# iNixie-Kit.net
KiCad netlist of a schematic drawn in Altium Designer
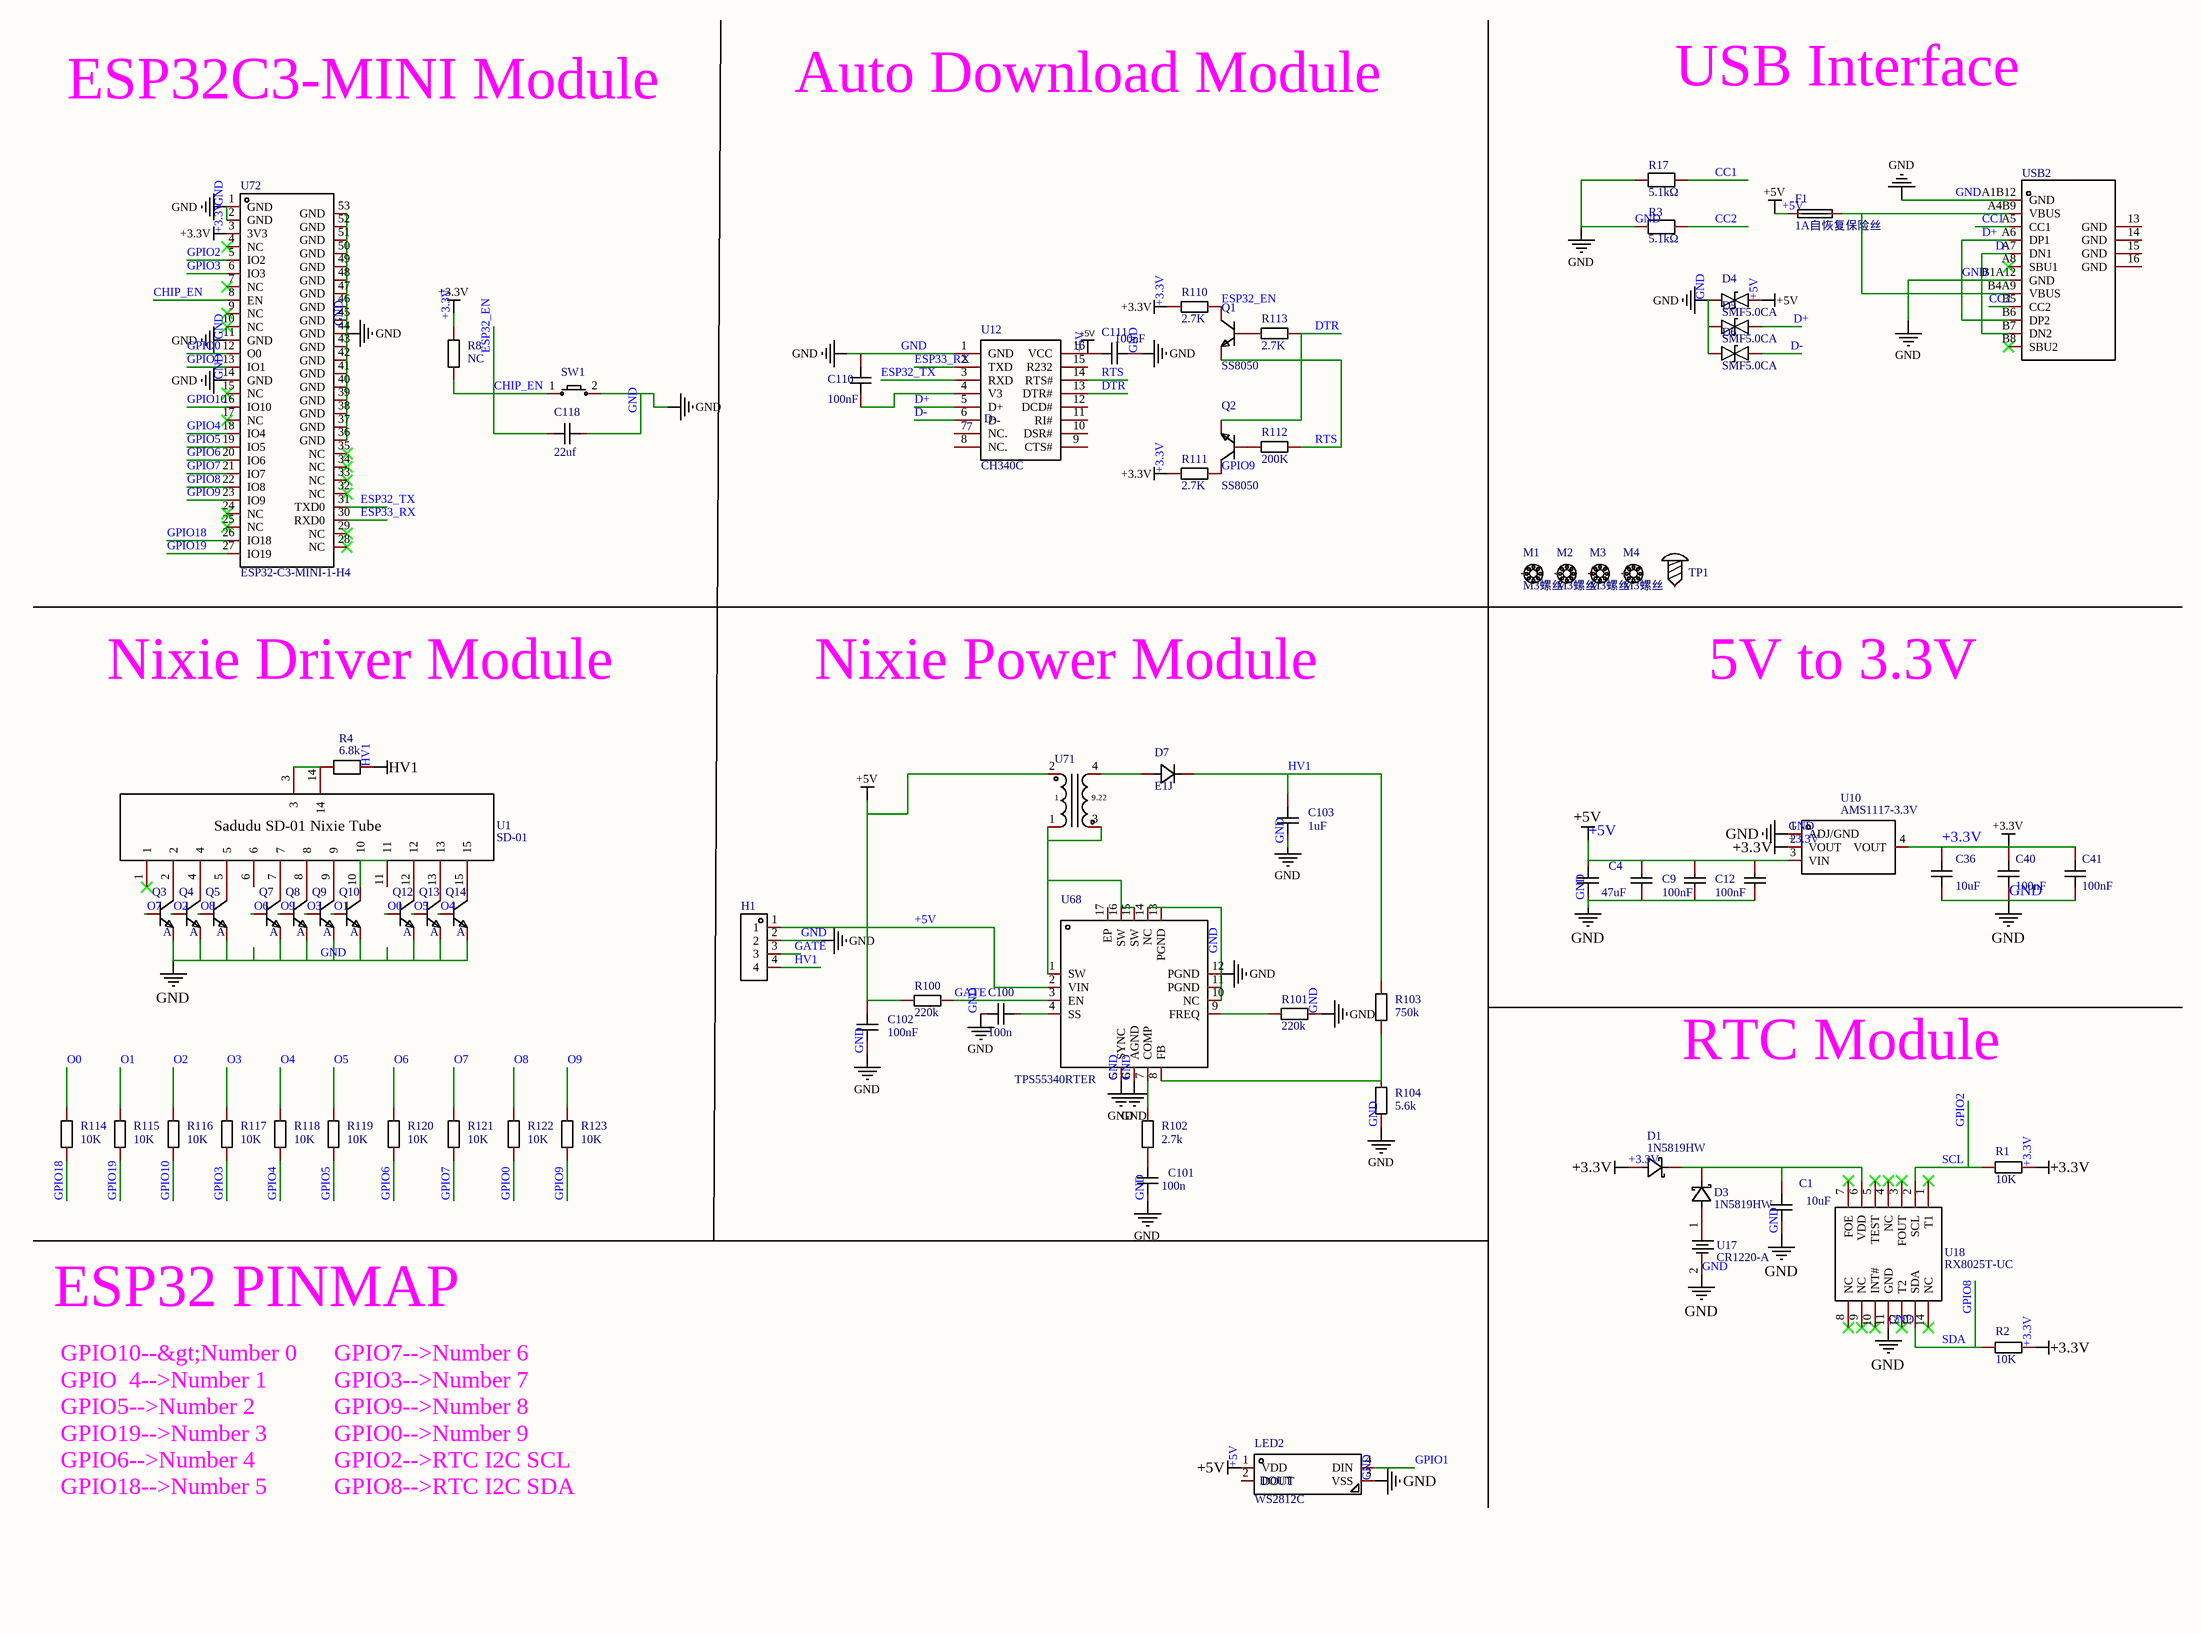
[diagram p0: iNixie-Kit.schdoc]

(export (version "E")
  (design (tool "Eeschema 10.0.6"))
  (components
    (comp (ref "C1")
      (value "10uF")
      (description "容值:10uF;精度:±20%;额定电压:10V;温度系数:X5R;")
      (fields
        (field (name "MANUFACTURER") "SAMSUNG(三星)")
        (field (name "MANUFACTURER PART") "CL10A106MP8NNNC")
      )
      (libsource (lib "altium-import") (part "root_1_CL10A106MP8NNNC_"))
    )
    (comp (ref "C4")
      (value "47uF")
      (description "容值:100nF;精度:±10%;额定电压:50V;温度系数:X7R;")
      (fields (field (name "NAME") "47uF"))
      (libsource (lib "altium-import") (part "root_1_CAP_1206_"))
    )
    (comp (ref "C9")
      (value "100nF")
      (description "容值:100nF;精度:±10%;额定电压:50V;温度系数:X7R;")
      (fields (field (name "MANUFACTURER") "FH(风华)") (field (name "MANUFACTURER PART") "0603B104K500NT"))
      (libsource (lib "altium-import") (part "root_3_0603B104K500NT_"))
    )
    (comp (ref "C12")
      (value "100nF")
      (description "容值:100nF;精度:±10%;额定电压:50V;温度系数:X7R;")
      (fields (field (name "MANUFACTURER") "FH(风华)") (field (name "MANUFACTURER PART") "0603B104K500NT"))
      (libsource (lib "altium-import") (part "root_3_0603B104K500NT_"))
    )
    (comp (ref "C13")
      (value "0603B104K500NT")
      (description "容值:100nF;精度:±10%;额定电压:50V;温度系数:X7R;")
      (fields (field (name "MANUFACTURER") "FH(风华)") (field (name "TOLERANCE") "±10%"))
      (libsource (lib "altium-import") (part "root_3_0603B104K500NT_"))
    )
    (comp (ref "C36")
      (value "10uF")
      (description "容值:10uF;精度:±20%;额定电压:10V;温度系数:X5R;")
      (fields
        (field (name "MANUFACTURER") "SAMSUNG(三星)")
        (field (name "MANUFACTURER PART") "CL10A106MP8NNNC")
      )
      (libsource (lib "altium-import") (part "root_1_CL10A106MP8NNNC_"))
    )
    (comp (ref "C40")
      (value "100nF")
      (description "容值:100nF;精度:±10%;额定电压:16V;温度系数:X7R;")
      (fields (field (name "NAME") "100nF"))
      (libsource (lib "altium-import") (part "root_1_CAP_0402_"))
    )
    (comp (ref "C41")
      (value "100nF")
      (description "容值:100nF;精度:±10%;额定电压:16V;温度系数:X7R;")
      (fields (field (name "NAME") "100nF"))
      (libsource (lib "altium-import") (part "root_1_CAP_0402_"))
    )
    (comp (ref "C100")
      (value "100n")
      (fields (field (name "NAME") "100n"))
      (libsource (lib "altium-import") (part "root_0_C0402_"))
    )
    (comp (ref "C101")
      (value "100n")
      (fields (field (name "NAME") "100n"))
      (libsource (lib "altium-import") (part "root_1_C0402_"))
    )
    (comp (ref "C102")
      (value "100nF")
      (fields (field (name "NAME") "100nF"))
      (libsource (lib "altium-import") (part "root_1_CAP_0603_"))
    )
    (comp (ref "C103")
      (value "1uF")
      (description "容值:1uF;精度:±10%;额定电压:50V;材质(温度系数):X7R;")
      (fields
        (field (name "NAME") "1uF")
        (field (name "MANUFACTURER") "SAMSUNG(三星)")
        (field (name "MANUFACTURER PART") "CL31B105KBHNNNE")
      )
      (libsource (lib "altium-import") (part "root_1_CL31B105KBHNNNE_"))
    )
    (comp (ref "C110")
      (value "100nF")
      (description "容值:100nF;精度:±10%;额定电压:50V;温度系数:X7R;")
      (fields (field (name "NAME") "100nF"))
      (libsource (lib "altium-import") (part "root_1_CAP_0603_"))
    )
    (comp (ref "C111")
      (value "100nF")
      (description "容值:100nF;精度:±10%;额定电压:50V;温度系数:X7R;")
      (fields (field (name "NAME") "100nF"))
      (libsource (lib "altium-import") (part "root_2_CAP_0603_"))
    )
    (comp (ref "C118")
      (value "22uf")
      (description "容值:100nF;精度:±10%;额定电压:16V;温度系数:X7R;")
      (fields (field (name "NAME") "22uf"))
      (libsource (lib "altium-import") (part "root_2_CAP_0402_"))
    )
    (comp (ref "D1")
      (value "1N5819HW")
      (fields (field (name "NAME") "1N5819HW") (field (name "MANUFACTURER") "TECH PUBLIC(台舟)"))
      (libsource (lib "altium-import") (part "root_2_1N5819HW_"))
    )
    (comp (ref "D3")
      (value "1N5819HW")
      (fields (field (name "NAME") "1N5819HW") (field (name "MANUFACTURER") "TECH PUBLIC(台舟)"))
      (libsource (lib "altium-import") (part "root_3_1N5819HW_"))
    )
    (comp (ref "D4")
      (value "SMF5.0CA")
      (description "极性:双向;反向截止电压(Vrwm):5V;击穿电压:6.4V;反向漏电流(Ir):800uA;峰值脉冲电流(Ipp)@10/1000s:21.7A;最大钳位电压:9.2V;")
      (fields (field (name "NAME") "SMF5.0CA") (field (name "MANUFACTURER") "FUXINSEMI(富芯森美)"))
      (libsource (lib "altium-import") (part "root_0_mirrored_SMF5.0CA_C908214_"))
    )
    (comp (ref "D5")
      (value "SMF5.0CA")
      (description "极性:双向;反向截止电压(Vrwm):5V;击穿电压:6.4V;反向漏电流(Ir):800uA;峰值脉冲电流(Ipp)@10/1000s:21.7A;最大钳位电压:9.2V;")
      (fields (field (name "NAME") "SMF5.0CA") (field (name "MANUFACTURER") "FUXINSEMI(富芯森美)"))
      (libsource (lib "altium-import") (part "root_0_mirrored_SMF5.0CA_C908214_"))
    )
    (comp (ref "D6")
      (value "SMF5.0CA")
      (description "极性:双向;反向截止电压(Vrwm):5V;击穿电压:6.4V;反向漏电流(Ir):800uA;峰值脉冲电流(Ipp)@10/1000s:21.7A;最大钳位电压:9.2V;")
      (fields (field (name "NAME") "SMF5.0CA") (field (name "MANUFACTURER") "FUXINSEMI(富芯森美)"))
      (libsource (lib "altium-import") (part "root_0_mirrored_SMF5.0CA_C908214_"))
    )
    (comp (ref "D7")
      (value "E1J")
      (description "二极管配置:-;直流反向耐压(Vr):600V;平均整流电流(Io):1A;正向压降(Vf):1.7V@1A;反向恢复时间(trr):35ns;")
      (fields (field (name "NAME") "E1J") (field (name "MANUFACTURER") "LGE(鲁光)"))
      (libsource (lib "altium-import") (part "root_2_E1J_"))
    )
    (comp (ref "F1")
      (value "1A自恢复保险丝")
      (fields (field (name "NAME") "1A自恢复保险丝"))
      (libsource (lib "altium-import") (part "root_0_1A自恢复保险丝_"))
    )
    (comp (ref "H1")
      (value "HDR-M_2.54_1x4P")
      (libsource (lib "altium-import") (part "root_0_mirrored_HDR-M_2.54_1x4P_"))
    )
    (comp (ref "LED2")
      (value "WS2812C")
      (description "发光颜色:RGB三色;")
      (fields
        (field (name "NAME") "WS2812C")
        (field (name "MANUFACTURER") "worldsemi")
        (field (name "NAME_1") "DOUT")
      )
      (libsource (lib "altium-import") (part "root_0_WS2812C_"))
    )
    (comp (ref "M1")
      (value "M3螺丝")
      (fields (field (name "NAME") "M3螺丝"))
      (libsource (lib "altium-import") (part "root_0_M3螺丝_"))
    )
    (comp (ref "M2")
      (value "M3螺丝")
      (fields (field (name "NAME") "M3螺丝"))
      (libsource (lib "altium-import") (part "root_0_M3螺丝_"))
    )
    (comp (ref "M3")
      (value "M3螺丝")
      (fields (field (name "NAME") "M3螺丝"))
      (libsource (lib "altium-import") (part "root_0_M3螺丝_"))
    )
    (comp (ref "M4")
      (value "M3螺丝")
      (fields (field (name "NAME") "M3螺丝"))
      (libsource (lib "altium-import") (part "root_0_M3螺丝_"))
    )
    (comp (ref "Q1")
      (value "SS8050")
      (fields (field (name "NAME") "SS8050") (field (name "MANUFACTURER") "CJ(江苏长电/长晶)"))
      (libsource (lib "altium-import") (part "root_0_mirrored_SS8050_C2150_"))
    )
    (comp (ref "Q2")
      (value "SS8050")
      (fields (field (name "NAME") "SS8050") (field (name "MANUFACTURER") "CJ(江苏长电/长晶)"))
      (libsource (lib "altium-import") (part "root_2_SS8050_C2150_"))
    )
    (comp (ref "Q3")
      (value "A")
      (fields
        (field (name "NAME") "A")
        (field (name "MANUFACTURER") "UTC")
        (field (name "MANUFACTURER PART") "MMBTA42G-AE3-R")
      )
      (libsource (lib "altium-import") (part "root_0_MMBTA42G-AE3-R_"))
    )
    (comp (ref "Q4")
      (value "A")
      (fields
        (field (name "NAME") "A")
        (field (name "MANUFACTURER") "UTC")
        (field (name "MANUFACTURER PART") "MMBTA42G-AE3-R")
      )
      (libsource (lib "altium-import") (part "root_0_MMBTA42G-AE3-R_"))
    )
    (comp (ref "Q5")
      (value "A")
      (fields
        (field (name "NAME") "A")
        (field (name "MANUFACTURER") "UTC")
        (field (name "MANUFACTURER PART") "MMBTA42G-AE3-R")
      )
      (libsource (lib "altium-import") (part "root_0_MMBTA42G-AE3-R_"))
    )
    (comp (ref "Q7")
      (value "A")
      (fields
        (field (name "NAME") "A")
        (field (name "MANUFACTURER") "UTC")
        (field (name "MANUFACTURER PART") "MMBTA42G-AE3-R")
      )
      (libsource (lib "altium-import") (part "root_0_MMBTA42G-AE3-R_"))
    )
    (comp (ref "Q8")
      (value "A")
      (fields
        (field (name "NAME") "A")
        (field (name "MANUFACTURER") "UTC")
        (field (name "MANUFACTURER PART") "MMBTA42G-AE3-R")
      )
      (libsource (lib "altium-import") (part "root_0_MMBTA42G-AE3-R_"))
    )
    (comp (ref "Q9")
      (value "A")
      (fields
        (field (name "NAME") "A")
        (field (name "MANUFACTURER") "UTC")
        (field (name "MANUFACTURER PART") "MMBTA42G-AE3-R")
      )
      (libsource (lib "altium-import") (part "root_0_MMBTA42G-AE3-R_"))
    )
    (comp (ref "Q10")
      (value "A")
      (fields
        (field (name "NAME") "A")
        (field (name "MANUFACTURER") "UTC")
        (field (name "MANUFACTURER PART") "MMBTA42G-AE3-R")
      )
      (libsource (lib "altium-import") (part "root_0_MMBTA42G-AE3-R_"))
    )
    (comp (ref "Q12")
      (value "A")
      (fields
        (field (name "NAME") "A")
        (field (name "MANUFACTURER") "UTC")
        (field (name "MANUFACTURER PART") "MMBTA42G-AE3-R")
      )
      (libsource (lib "altium-import") (part "root_0_MMBTA42G-AE3-R_"))
    )
    (comp (ref "Q13")
      (value "A")
      (fields
        (field (name "NAME") "A")
        (field (name "MANUFACTURER") "UTC")
        (field (name "MANUFACTURER PART") "MMBTA42G-AE3-R")
      )
      (libsource (lib "altium-import") (part "root_0_MMBTA42G-AE3-R_"))
    )
    (comp (ref "Q14")
      (value "A")
      (fields
        (field (name "NAME") "A")
        (field (name "MANUFACTURER") "UTC")
        (field (name "MANUFACTURER PART") "MMBTA42G-AE3-R")
      )
      (libsource (lib "altium-import") (part "root_0_MMBTA42G-AE3-R_"))
    )
    (comp (ref "R1")
      (value "10K")
      (fields (field (name "NAME") "10K"))
      (libsource (lib "altium-import") (part "root_0_Res_0402_"))
    )
    (comp (ref "R2")
      (value "10K")
      (fields (field (name "NAME") "10K"))
      (libsource (lib "altium-import") (part "root_0_Res_0402_"))
    )
    (comp (ref "R3")
      (value "5.1kΩ")
      (description "温度系数:±25ppm/℃;精度:±0.1%;功率:100mW;阻值:5.1kΩ;最大工作电压:50V;工作温度范围:-55℃~+155℃;")
      (fields (field (name "MANUFACTURER") "FH(风华)") (field (name "MANUFACTURER PART") "TD03G5101BT"))
      (libsource (lib "altium-import") (part "root_2_mirrored_td03g5101bt_"))
    )
    (comp (ref "R4")
      (value "6.8k")
      (fields (field (name "NAME") "6.8k"))
      (libsource (lib "altium-import") (part "root_0_5k_"))
    )
    (comp (ref "R8")
      (value "NC")
      (fields (field (name "NAME") "NC"))
      (libsource (lib "altium-import") (part "root_1_Res_0402_"))
    )
    (comp (ref "R17")
      (value "5.1kΩ")
      (description "温度系数:±25ppm/℃;精度:±0.1%;功率:100mW;阻值:5.1kΩ;最大工作电压:50V;工作温度范围:-55℃~+155℃;")
      (fields (field (name "MANUFACTURER") "FH(风华)") (field (name "MANUFACTURER PART") "TD03G5101BT"))
      (libsource (lib "altium-import") (part "root_2_mirrored_td03g5101bt_"))
    )
    (comp (ref "R100")
      (value "220k")
      (fields (field (name "NAME") "220k"))
      (libsource (lib "altium-import") (part "root_0_Res_0402_"))
    )
    (comp (ref "R101")
      (value "220k")
      (fields (field (name "NAME") "220k"))
      (libsource (lib "altium-import") (part "root_0_Res_0402_"))
    )
    (comp (ref "R102")
      (value "2.7k")
      (fields (field (name "NAME") "2.7k"))
      (libsource (lib "altium-import") (part "root_1_Res_0402_"))
    )
    (comp (ref "R103")
      (value "750k")
      (fields (field (name "NAME") "750k"))
      (libsource (lib "altium-import") (part "root_1_Res_0402_"))
    )
    (comp (ref "R104")
      (value "5.6k")
      (fields (field (name "NAME") "5.6k"))
      (libsource (lib "altium-import") (part "root_1_Res_0402_"))
    )
    (comp (ref "R110")
      (value "2.7K")
      (fields (field (name "NAME") "2.7K"))
      (libsource (lib "altium-import") (part "root_0_Res_0402_"))
    )
    (comp (ref "R111")
      (value "2.7K")
      (fields (field (name "NAME") "2.7K"))
      (libsource (lib "altium-import") (part "root_0_Res_0402_"))
    )
    (comp (ref "R112")
      (value "200K")
      (fields (field (name "NAME") "200K"))
      (libsource (lib "altium-import") (part "root_0_Res_0402_"))
    )
    (comp (ref "R113")
      (value "2.7K")
      (fields (field (name "NAME") "2.7K"))
      (libsource (lib "altium-import") (part "root_0_Res_0402_"))
    )
    (comp (ref "R114")
      (value "10K")
      (fields (field (name "NAME") "10K"))
      (libsource (lib "altium-import") (part "root_1_Res_0402_"))
    )
    (comp (ref "R115")
      (value "10K")
      (fields (field (name "NAME") "10K"))
      (libsource (lib "altium-import") (part "root_1_Res_0402_"))
    )
    (comp (ref "R116")
      (value "10K")
      (fields (field (name "NAME") "10K"))
      (libsource (lib "altium-import") (part "root_1_Res_0402_"))
    )
    (comp (ref "R117")
      (value "10K")
      (fields (field (name "NAME") "10K"))
      (libsource (lib "altium-import") (part "root_1_Res_0402_"))
    )
    (comp (ref "R118")
      (value "10K")
      (fields (field (name "NAME") "10K"))
      (libsource (lib "altium-import") (part "root_1_Res_0402_"))
    )
    (comp (ref "R119")
      (value "10K")
      (fields (field (name "NAME") "10K"))
      (libsource (lib "altium-import") (part "root_1_Res_0402_"))
    )
    (comp (ref "R120")
      (value "10K")
      (fields (field (name "NAME") "10K"))
      (libsource (lib "altium-import") (part "root_1_Res_0402_"))
    )
    (comp (ref "R121")
      (value "10K")
      (fields (field (name "NAME") "10K"))
      (libsource (lib "altium-import") (part "root_1_Res_0402_"))
    )
    (comp (ref "R122")
      (value "10K")
      (fields (field (name "NAME") "10K"))
      (libsource (lib "altium-import") (part "root_1_Res_0402_"))
    )
    (comp (ref "R123")
      (value "10K")
      (fields (field (name "NAME") "10K"))
      (libsource (lib "altium-import") (part "root_1_Res_0402_"))
    )
    (comp (ref "SW1")
      (value "Key_SMD_3.6x6.1x2.5")
      (libsource (lib "altium-import") (part "root_0_Key_SMD_3.6x6.1x2.5_"))
    )
    (comp (ref "TP1") (value "M2螺丝") (libsource (lib "altium-import") (part "root_0_M2螺丝_")))
    (comp (ref "U1")
      (value "SD-01")
      (fields (field (name "NAME") "SD-01") (field (name "MANUFACTURER") "Sadudu"))
      (libsource (lib "altium-import") (part "root_0_SD-01_"))
    )
    (comp (ref "U10")
      (value "AMS1117-3.3V")
      (fields (field (name "NAME") "AMS1117-3.3V") (field (name "MANUFACTURER") "WPMtek(维攀微)"))
      (libsource (lib "altium-import") (part "root_0_AMS1117-3.3V_"))
    )
    (comp (ref "U12")
      (value "CH340C")
      (description "应用功能:Transceiver;接口协议:USB 2.0;数据速率:2Mbps;供电电压:3.3V；5V;")
      (fields
        (field (name "NAME") "CH340C")
        (field (name "MANUFACTURER") "WCH(南京沁恒)")
        (field (name "NAME_1") "D-")
        (field (name "NUMBER") "7")
      )
      (libsource (lib "altium-import") (part "root_0_CH340C_"))
    )
    (comp (ref "U17")
      (value "CR1220-A")
      (fields (field (name "NAME") "CR1220-A"))
      (libsource (lib "altium-import") (part "root_3_CR1220-A_"))
    )
    (comp (ref "U18")
      (value "RX8025T-UC")
      (fields (field (name "NAME") "RX8025T-UC") (field (name "MANUFACTURER") "EPSON"))
      (libsource (lib "altium-import") (part "root_3_RX8025T-UC_"))
    )
    (comp (ref "U68")
      (value "TPS55340RTER")
      (fields (field (name "NAME") "TPS55340RTER") (field (name "MANUFACTURER") "TI(德州仪器)"))
      (libsource (lib "altium-import") (part "root_0_TPS55340RTER_"))
    )
    (comp (ref "U71") (value "T3") (libsource (lib "altium-import") (part "root_0_T3_")))
    (comp (ref "U72")
      (value "ESP32-C3-MINI-1-H4")
      (fields (field (name "NAME") "ESP32-C3-MINI-1-H4") (field (name "MANUFACTURER") "ESPRESSIF(乐鑫)"))
      (libsource (lib "altium-import") (part "root_0_ESP32-C3-MINI-1-H4_C2935306_"))
    )
    (comp (ref "USB2")
      (value "typec-304-bcp16")
      (description "连接器类型:Type-C;标准:USB 3.1;公母:母座;触点数量:16.0;端口数量:1;安装方式:卧贴;额定电流 - 电源:3A;工作温度范围:-25~+85;焊接温度(最大值):260;")
      (fields (field (name "MANUFACTURER") "XUNPU(讯普)") (field (name "MANUFACTURER PART") "TYPEC-304-BCP16"))
      (libsource (lib "altium-import") (part "root_0_typec-304-bcp16_"))
    )
  )
  (nets
    (net (code "1") (name "+3.3V") (class "Default")
      (node (ref "C36") (pin "2") (pinfunction "2_2") (pintype "passive"))
      (node (ref "C40") (pin "2") (pinfunction "2_2") (pintype "passive"))
      (node (ref "C41") (pin "2") (pinfunction "2_2") (pintype "passive"))
      (node (ref "D1") (pin "2") (pinfunction "A_2") (pintype "passive"))
      (node (ref "R1") (pin "2") (pinfunction "2_2") (pintype "passive"))
      (node (ref "R110") (pin "1") (pinfunction "1_1") (pintype "passive"))
      (node (ref "R111") (pin "1") (pinfunction "1_1") (pintype "passive"))
      (node (ref "R2") (pin "2") (pinfunction "2_2") (pintype "passive"))
      (node (ref "R8") (pin "2") (pinfunction "2_2") (pintype "passive"))
      (node (ref "U10") (pin "2") (pinfunction "VOUT_2") (pintype "passive"))
      (node (ref "U10") (pin "4") (pinfunction "VOUT_4") (pintype "passive"))
      (node (ref "U72") (pin "3") (pinfunction "3V3_3") (pintype "passive"))
    )
    (net (code "2") (name "+5V") (class "Default")
      (node (ref "C102") (pin "2") (pinfunction "2_2") (pintype "passive"))
      (node (ref "C111") (pin "2") (pinfunction "2_2") (pintype "passive"))
      (node (ref "C12") (pin "1") (pinfunction "1_1") (pintype "passive"))
      (node (ref "C13") (pin "1") (pinfunction "1_1") (pintype "passive"))
      (node (ref "C4") (pin "2") (pinfunction "2_2") (pintype "passive"))
      (node (ref "C9") (pin "1") (pinfunction "1_1") (pintype "passive"))
      (node (ref "D4") (pin "1") (pinfunction "1_1") (pintype "passive"))
      (node (ref "F1") (pin "1") (pinfunction "1_1") (pintype "passive"))
      (node (ref "H1") (pin "1") (pinfunction "1_1") (pintype "passive"))
      (node (ref "LED2") (pin "1") (pinfunction "VDD_1") (pintype "passive"))
      (node (ref "R100") (pin "1") (pinfunction "1_1") (pintype "passive"))
      (node (ref "U10") (pin "3") (pinfunction "VIN_3") (pintype "passive"))
      (node (ref "U12") (pin "16") (pinfunction "VCC_16") (pintype "passive"))
      (node (ref "U68") (pin "2") (pinfunction "VIN_2") (pintype "passive"))
      (node (ref "U71") (pin "2") (pinfunction "1_2") (pintype "passive"))
    )
    (net (code "3") (name "/CC1") (class "Default")
      (node (ref "R17") (pin "2") (pinfunction "2_2") (pintype "passive"))
      (node (ref "USB2") (pin "A5") (pinfunction "CC1_A5") (pintype "passive"))
    )
    (net (code "4") (name "/CC2") (class "Default")
      (node (ref "R3") (pin "2") (pinfunction "2_2") (pintype "passive"))
      (node (ref "USB2") (pin "B5") (pinfunction "CC2_B5") (pintype "passive"))
    )
    (net (code "5") (name "/CHIP_EN") (class "Default")
      (node (ref "C118") (pin "2") (pinfunction "2_2") (pintype "passive"))
      (node (ref "Q1") (pin "3") (pinfunction "C_3") (pintype "passive"))
      (node (ref "R110") (pin "2") (pinfunction "2_2") (pintype "passive"))
      (node (ref "R8") (pin "1") (pinfunction "1_1") (pintype "passive"))
      (node (ref "SW1") (pin "1") (pinfunction "1_1") (pintype "passive"))
      (node (ref "U72") (pin "8") (pinfunction "EN_8") (pintype "passive"))
    )
    (net (code "6") (name "/D-") (class "Default")
      (node (ref "D6") (pin "1") (pinfunction "1_1") (pintype "passive"))
      (node (ref "U12") (pin "6") (pinfunction "D-_6") (pintype "passive"))
      (node (ref "USB2") (pin "A7") (pinfunction "DN1_A7") (pintype "passive"))
      (node (ref "USB2") (pin "B7") (pinfunction "DN2_B7") (pintype "passive"))
    )
    (net (code "7") (name "/DTR") (class "Default")
      (node (ref "Q2") (pin "2") (pinfunction "E_2") (pintype "passive"))
      (node (ref "R113") (pin "2") (pinfunction "2_2") (pintype "passive"))
      (node (ref "U12") (pin "13") (pinfunction "DTR#_13") (pintype "passive"))
    )
    (net (code "8") (name "/ESP32_TX") (class "Default")
      (node (ref "U12") (pin "3") (pinfunction "RXD_3") (pintype "passive"))
      (node (ref "U72") (pin "31") (pinfunction "TXD0_31") (pintype "passive"))
    )
    (net (code "9") (name "/ESP33_RX") (class "Default")
      (node (ref "U12") (pin "2") (pinfunction "TXD_2") (pintype "passive"))
      (node (ref "U72") (pin "30") (pinfunction "RXD0_30") (pintype "passive"))
    )
    (net (code "10") (name "/GATE") (class "Default")
      (node (ref "H1") (pin "3") (pinfunction "3_3") (pintype "passive"))
      (node (ref "R100") (pin "2") (pinfunction "2_2") (pintype "passive"))
      (node (ref "U68") (pin "3") (pinfunction "EN_3") (pintype "passive"))
    )
    (net (code "11") (name "/GPIO0") (class "Default")
      (node (ref "R122") (pin "1") (pinfunction "1_1") (pintype "passive"))
      (node (ref "U72") (pin "12") (pinfunction "O0_12") (pintype "passive"))
    )
    (net (code "12") (name "/GPIO1") (class "Default")
      (node (ref "LED2") (pin "4") (pinfunction "DIN_4") (pintype "passive"))
      (node (ref "U72") (pin "13") (pinfunction "IO1_13") (pintype "passive"))
    )
    (net (code "13") (name "/GPIO2") (class "Default")
      (node (ref "R1") (pin "1") (pinfunction "1_1") (pintype "passive"))
      (node (ref "U18") (pin "2") (pinfunction "SCL_2") (pintype "passive"))
      (node (ref "U72") (pin "5") (pinfunction "IO2_5") (pintype "passive"))
    )
    (net (code "14") (name "/GPIO3") (class "Default")
      (node (ref "R117") (pin "1") (pinfunction "1_1") (pintype "passive"))
      (node (ref "U72") (pin "6") (pinfunction "IO3_6") (pintype "passive"))
    )
    (net (code "15") (name "/GPIO4") (class "Default")
      (node (ref "R118") (pin "1") (pinfunction "1_1") (pintype "passive"))
      (node (ref "U72") (pin "18") (pinfunction "IO4_18") (pintype "passive"))
    )
    (net (code "16") (name "/GPIO5") (class "Default")
      (node (ref "R119") (pin "1") (pinfunction "1_1") (pintype "passive"))
      (node (ref "U72") (pin "19") (pinfunction "IO5_19") (pintype "passive"))
    )
    (net (code "17") (name "/GPIO6") (class "Default")
      (node (ref "R120") (pin "1") (pinfunction "1_1") (pintype "passive"))
      (node (ref "U72") (pin "20") (pinfunction "IO6_20") (pintype "passive"))
    )
    (net (code "18") (name "/GPIO7") (class "Default")
      (node (ref "R121") (pin "1") (pinfunction "1_1") (pintype "passive"))
      (node (ref "U72") (pin "21") (pinfunction "IO7_21") (pintype "passive"))
    )
    (net (code "19") (name "/GPIO8") (class "Default")
      (node (ref "R2") (pin "1") (pinfunction "1_1") (pintype "passive"))
      (node (ref "U18") (pin "13") (pinfunction "SDA_13") (pintype "passive"))
      (node (ref "U72") (pin "22") (pinfunction "IO8_22") (pintype "passive"))
    )
    (net (code "20") (name "/GPIO9") (class "Default")
      (node (ref "Q2") (pin "3") (pinfunction "C_3") (pintype "passive"))
      (node (ref "R111") (pin "2") (pinfunction "2_2") (pintype "passive"))
      (node (ref "R123") (pin "1") (pinfunction "1_1") (pintype "passive"))
      (node (ref "U72") (pin "23") (pinfunction "IO9_23") (pintype "passive"))
    )
    (net (code "21") (name "/GPIO10") (class "Default")
      (node (ref "R116") (pin "1") (pinfunction "1_1") (pintype "passive"))
      (node (ref "U72") (pin "16") (pinfunction "IO10_16") (pintype "passive"))
    )
    (net (code "22") (name "/GPIO18") (class "Default")
      (node (ref "R114") (pin "1") (pinfunction "1_1") (pintype "passive"))
      (node (ref "U72") (pin "26") (pinfunction "IO18_26") (pintype "passive"))
    )
    (net (code "23") (name "/GPIO19") (class "Default")
      (node (ref "R115") (pin "1") (pinfunction "1_1") (pintype "passive"))
      (node (ref "U72") (pin "27") (pinfunction "IO19_27") (pintype "passive"))
    )
    (net (code "24") (name "/O0") (class "Default")
      (node (ref "Q12") (pin "2") (pinfunction "B_2") (pintype "passive"))
      (node (ref "R114") (pin "2") (pinfunction "2_2") (pintype "passive"))
    )
    (net (code "25") (name "/O1") (class "Default")
      (node (ref "Q10") (pin "2") (pinfunction "B_2") (pintype "passive"))
      (node (ref "R115") (pin "2") (pinfunction "2_2") (pintype "passive"))
    )
    (net (code "26") (name "/O2") (class "Default")
      (node (ref "Q4") (pin "2") (pinfunction "B_2") (pintype "passive"))
      (node (ref "R116") (pin "2") (pinfunction "2_2") (pintype "passive"))
    )
    (net (code "27") (name "/O3") (class "Default")
      (node (ref "Q9") (pin "2") (pinfunction "B_2") (pintype "passive"))
      (node (ref "R117") (pin "2") (pinfunction "2_2") (pintype "passive"))
    )
    (net (code "28") (name "/O4") (class "Default")
      (node (ref "Q14") (pin "2") (pinfunction "B_2") (pintype "passive"))
      (node (ref "R118") (pin "2") (pinfunction "2_2") (pintype "passive"))
    )
    (net (code "29") (name "/O5") (class "Default")
      (node (ref "Q13") (pin "2") (pinfunction "B_2") (pintype "passive"))
      (node (ref "R119") (pin "2") (pinfunction "2_2") (pintype "passive"))
    )
    (net (code "30") (name "/O6") (class "Default")
      (node (ref "Q7") (pin "2") (pinfunction "B_2") (pintype "passive"))
      (node (ref "R120") (pin "2") (pinfunction "2_2") (pintype "passive"))
    )
    (net (code "31") (name "/O7") (class "Default")
      (node (ref "Q3") (pin "2") (pinfunction "B_2") (pintype "passive"))
      (node (ref "R121") (pin "2") (pinfunction "2_2") (pintype "passive"))
    )
    (net (code "32") (name "/O8") (class "Default")
      (node (ref "Q5") (pin "2") (pinfunction "B_2") (pintype "passive"))
      (node (ref "R122") (pin "2") (pinfunction "2_2") (pintype "passive"))
    )
    (net (code "33") (name "/O9") (class "Default")
      (node (ref "Q8") (pin "2") (pinfunction "B_2") (pintype "passive"))
      (node (ref "R123") (pin "2") (pinfunction "2_2") (pintype "passive"))
    )
    (net (code "34") (name "/RTS") (class "Default")
      (node (ref "Q1") (pin "2") (pinfunction "E_2") (pintype "passive"))
      (node (ref "R112") (pin "2") (pinfunction "2_2") (pintype "passive"))
      (node (ref "U12") (pin "14") (pinfunction "RTS#_14") (pintype "passive"))
    )
    (net (code "35") (name "GND") (class "Default")
      (node (ref "C1") (pin "1") (pinfunction "1_1") (pintype "passive"))
      (node (ref "C100") (pin "1") (pinfunction "1_1") (pintype "passive"))
      (node (ref "C101") (pin "1") (pinfunction "1_1") (pintype "passive"))
      (node (ref "C102") (pin "1") (pinfunction "1_1") (pintype "passive"))
      (node (ref "C103") (pin "1") (pinfunction "1_1") (pintype "passive"))
      (node (ref "C110") (pin "2") (pinfunction "2_2") (pintype "passive"))
      (node (ref "C111") (pin "1") (pinfunction "1_1") (pintype "passive"))
      (node (ref "C118") (pin "1") (pinfunction "1_1") (pintype "passive"))
      (node (ref "C12") (pin "2") (pinfunction "2_2") (pintype "passive"))
      (node (ref "C13") (pin "2") (pinfunction "2_2") (pintype "passive"))
      (node (ref "C36") (pin "1") (pinfunction "1_1") (pintype "passive"))
      (node (ref "C4") (pin "1") (pinfunction "1_1") (pintype "passive"))
      (node (ref "C40") (pin "1") (pinfunction "1_1") (pintype "passive"))
      (node (ref "C41") (pin "1") (pinfunction "1_1") (pintype "passive"))
      (node (ref "C9") (pin "2") (pinfunction "2_2") (pintype "passive"))
      (node (ref "D4") (pin "2") (pinfunction "2_2") (pintype "passive"))
      (node (ref "D5") (pin "1") (pinfunction "1_1") (pintype "passive"))
      (node (ref "D5") (pin "2") (pinfunction "2_2") (pintype "passive"))
      (node (ref "D6") (pin "2") (pinfunction "2_2") (pintype "passive"))
      (node (ref "H1") (pin "2") (pinfunction "2_2") (pintype "passive"))
      (node (ref "LED2") (pin "3") (pinfunction "VSS_3") (pintype "passive"))
      (node (ref "Q10") (pin "1") (pinfunction "E_1") (pintype "passive"))
      (node (ref "Q12") (pin "1") (pinfunction "E_1") (pintype "passive"))
      (node (ref "Q13") (pin "1") (pinfunction "E_1") (pintype "passive"))
      (node (ref "Q14") (pin "1") (pinfunction "E_1") (pintype "passive"))
      (node (ref "Q3") (pin "1") (pinfunction "E_1") (pintype "passive"))
      (node (ref "Q4") (pin "1") (pinfunction "E_1") (pintype "passive"))
      (node (ref "Q5") (pin "1") (pinfunction "E_1") (pintype "passive"))
      (node (ref "Q7") (pin "1") (pinfunction "E_1") (pintype "passive"))
      (node (ref "Q8") (pin "1") (pinfunction "E_1") (pintype "passive"))
      (node (ref "Q9") (pin "1") (pinfunction "E_1") (pintype "passive"))
      (node (ref "R101") (pin "2") (pinfunction "2_2") (pintype "passive"))
      (node (ref "R104") (pin "1") (pinfunction "1_1") (pintype "passive"))
      (node (ref "R17") (pin "1") (pinfunction "1_1") (pintype "passive"))
      (node (ref "R3") (pin "1") (pinfunction "1_1") (pintype "passive"))
      (node (ref "SW1") (pin "2") (pinfunction "2_2") (pintype "passive"))
      (node (ref "U10") (pin "1") (pinfunction "ADJ/GND_1") (pintype "passive"))
      (node (ref "U12") (pin "1") (pinfunction "GND_1") (pintype "passive"))
      (node (ref "U12") (pin "5") (pinfunction "D+_5") (pintype "passive"))
      (node (ref "U17") (pin "2") (pinfunction "2_2") (pintype "passive"))
      (node (ref "U18") (pin "11") (pinfunction "GND_11") (pintype "passive"))
      (node (ref "U68") (pin "10") (pinfunction "NC_10") (pintype "passive"))
      (node (ref "U68") (pin "11") (pinfunction "PGND_11") (pintype "passive"))
      (node (ref "U68") (pin "12") (pinfunction "PGND_12") (pintype "passive"))
      (node (ref "U68") (pin "13") (pinfunction "PGND_13") (pintype "passive"))
      (node (ref "U68") (pin "14") (pinfunction "NC_14") (pintype "passive"))
      (node (ref "U68") (pin "5") (pinfunction "SYNC_5") (pintype "passive"))
      (node (ref "U68") (pin "6") (pinfunction "AGND_6") (pintype "passive"))
      (node (ref "U72") (pin "1") (pinfunction "GND_1") (pintype "passive"))
      (node (ref "U72") (pin "11") (pinfunction "GND_11") (pintype "passive"))
      (node (ref "U72") (pin "14") (pinfunction "GND_14") (pintype "passive"))
      (node (ref "U72") (pin "2") (pinfunction "GND_2") (pintype "passive"))
      (node (ref "U72") (pin "36") (pinfunction "GND_36") (pintype "passive"))
      (node (ref "U72") (pin "37") (pinfunction "GND_37") (pintype "passive"))
      (node (ref "U72") (pin "38") (pinfunction "GND_38") (pintype "passive"))
      (node (ref "U72") (pin "39") (pinfunction "GND_39") (pintype "passive"))
      (node (ref "U72") (pin "40") (pinfunction "GND_40") (pintype "passive"))
      (node (ref "U72") (pin "41") (pinfunction "GND_41") (pintype "passive"))
      (node (ref "U72") (pin "42") (pinfunction "GND_42") (pintype "passive"))
      (node (ref "U72") (pin "43") (pinfunction "GND_43") (pintype "passive"))
      (node (ref "U72") (pin "44") (pinfunction "GND_44") (pintype "passive"))
      (node (ref "U72") (pin "45") (pinfunction "GND_45") (pintype "passive"))
      (node (ref "U72") (pin "46") (pinfunction "GND_46") (pintype "passive"))
      (node (ref "U72") (pin "47") (pinfunction "GND_47") (pintype "passive"))
      (node (ref "U72") (pin "48") (pinfunction "GND_48") (pintype "passive"))
      (node (ref "U72") (pin "49") (pinfunction "GND_49") (pintype "passive"))
      (node (ref "U72") (pin "50") (pinfunction "GND_50") (pintype "passive"))
      (node (ref "U72") (pin "51") (pinfunction "GND_51") (pintype "passive"))
      (node (ref "U72") (pin "52") (pinfunction "GND_52") (pintype "passive"))
      (node (ref "U72") (pin "53") (pinfunction "GND_53") (pintype "passive"))
      (node (ref "USB2") (pin "A1B12") (pinfunction "GND_A1B12") (pintype "passive"))
      (node (ref "USB2") (pin "A6") (pinfunction "DP1_A6") (pintype "passive"))
      (node (ref "USB2") (pin "B1A12") (pinfunction "GND_B1A12") (pintype "passive"))
      (node (ref "USB2") (pin "B6") (pinfunction "DP2_B6") (pintype "passive"))
    )
    (net (code "36") (name "HV1") (class "Default")
      (node (ref "C103") (pin "2") (pinfunction "2_2") (pintype "passive"))
      (node (ref "D7") (pin "1") (pinfunction "K_1") (pintype "passive"))
      (node (ref "H1") (pin "4") (pinfunction "4_4") (pintype "passive"))
      (node (ref "R103") (pin "2") (pinfunction "2_2") (pintype "passive"))
      (node (ref "R4") (pin "2") (pinfunction "2_2") (pintype "passive"))
    )
    (net (code "37") (name "Net-(C101-Pad2)") (class "Default")
      (node (ref "C101") (pin "2") (pinfunction "2_2") (pintype "passive"))
      (node (ref "R102") (pin "1") (pinfunction "1_1") (pintype "passive"))
    )
    (net (code "38") (name "Net-(D1-K)") (class "Default")
      (node (ref "C1") (pin "2") (pinfunction "2_2") (pintype "passive"))
      (node (ref "D1") (pin "1") (pinfunction "K_1") (pintype "passive"))
      (node (ref "D3") (pin "1") (pinfunction "K_1") (pintype "passive"))
      (node (ref "U18") (pin "6") (pinfunction "VDD_6") (pintype "passive"))
    )
    (net (code "39") (name "Net-(D3-A)") (class "Default")
      (node (ref "D3") (pin "2") (pinfunction "A_2") (pintype "passive"))
      (node (ref "U17") (pin "1") (pinfunction "1_1") (pintype "passive"))
    )
    (net (code "40") (name "Net-(D7-A)") (class "Default")
      (node (ref "D7") (pin "2") (pinfunction "A_2") (pintype "passive"))
      (node (ref "U71") (pin "4") (pinfunction "3_4") (pintype "passive"))
    )
    (net (code "41") (name "Net-(F1-Pad2)") (class "Default")
      (node (ref "F1") (pin "2") (pinfunction "2_2") (pintype "passive"))
      (node (ref "USB2") (pin "A4B9") (pinfunction "VBUS_A4B9") (pintype "passive"))
      (node (ref "USB2") (pin "B4A9") (pinfunction "VBUS_B4A9") (pintype "passive"))
    )
    (net (code "42") (name "Net-(Q1-B)") (class "Default")
      (node (ref "Q1") (pin "1") (pinfunction "B_1") (pintype "passive"))
      (node (ref "R113") (pin "1") (pinfunction "1_1") (pintype "passive"))
    )
    (net (code "43") (name "Net-(Q2-B)") (class "Default")
      (node (ref "Q2") (pin "1") (pinfunction "B_1") (pintype "passive"))
      (node (ref "R112") (pin "1") (pinfunction "1_1") (pintype "passive"))
    )
    (net (code "44") (name "Net-(Q3-C)") (class "Default")
      (node (ref "Q3") (pin "3") (pinfunction "C_3") (pintype "passive"))
      (node (ref "U1") (pin "2") (pinfunction "2_2") (pintype "passive"))
    )
    (net (code "45") (name "Net-(Q4-C)") (class "Default")
      (node (ref "Q4") (pin "3") (pinfunction "C_3") (pintype "passive"))
      (node (ref "U1") (pin "4") (pinfunction "4_4") (pintype "passive"))
    )
    (net (code "46") (name "Net-(Q5-C)") (class "Default")
      (node (ref "Q5") (pin "3") (pinfunction "C_3") (pintype "passive"))
      (node (ref "U1") (pin "5") (pinfunction "5_5") (pintype "passive"))
    )
    (net (code "47") (name "Net-(Q7-C)") (class "Default")
      (node (ref "Q7") (pin "3") (pinfunction "C_3") (pintype "passive"))
      (node (ref "U1") (pin "7") (pinfunction "7_7") (pintype "passive"))
    )
    (net (code "48") (name "Net-(Q8-C)") (class "Default")
      (node (ref "Q8") (pin "3") (pinfunction "C_3") (pintype "passive"))
      (node (ref "U1") (pin "8") (pinfunction "8_8") (pintype "passive"))
    )
    (net (code "49") (name "Net-(Q9-C)") (class "Default")
      (node (ref "Q9") (pin "3") (pinfunction "C_3") (pintype "passive"))
      (node (ref "U1") (pin "9") (pinfunction "9_9") (pintype "passive"))
    )
    (net (code "50") (name "Net-(Q10-C)") (class "Default")
      (node (ref "Q10") (pin "3") (pinfunction "C_3") (pintype "passive"))
      (node (ref "U1") (pin "10") (pinfunction "10_10") (pintype "passive"))
    )
    (net (code "51") (name "Net-(Q12-C)") (class "Default")
      (node (ref "Q12") (pin "3") (pinfunction "C_3") (pintype "passive"))
      (node (ref "U1") (pin "12") (pinfunction "12_12") (pintype "passive"))
    )
    (net (code "52") (name "Net-(Q13-C)") (class "Default")
      (node (ref "Q13") (pin "3") (pinfunction "C_3") (pintype "passive"))
      (node (ref "U1") (pin "13") (pinfunction "13_13") (pintype "passive"))
    )
    (net (code "53") (name "Net-(Q14-C)") (class "Default")
      (node (ref "Q14") (pin "3") (pinfunction "C_3") (pintype "passive"))
      (node (ref "U1") (pin "15") (pinfunction "15_15") (pintype "passive"))
    )
    (net (code "54") (name "Net-(R4-Pad1)") (class "Default")
      (node (ref "R4") (pin "1") (pinfunction "1_1") (pintype "passive"))
      (node (ref "U1") (pin "14") (pinfunction "14_14") (pintype "passive"))
      (node (ref "U1") (pin "3") (pinfunction "3_3") (pintype "passive"))
    )
    (net (code "55") (name "Net-(U12-V3)") (class "Default")
      (node (ref "C110") (pin "1") (pinfunction "1_1") (pintype "passive"))
      (node (ref "U12") (pin "4") (pinfunction "V3_4") (pintype "passive"))
    )
    (net (code "56") (name "Net-(U68-COMP)") (class "Default")
      (node (ref "R102") (pin "2") (pinfunction "2_2") (pintype "passive"))
      (node (ref "U68") (pin "7") (pinfunction "COMP_7") (pintype "passive"))
    )
    (net (code "57") (name "Net-(U68-FB)") (class "Default")
      (node (ref "R103") (pin "1") (pinfunction "1_1") (pintype "passive"))
      (node (ref "R104") (pin "2") (pinfunction "2_2") (pintype "passive"))
      (node (ref "U68") (pin "8") (pinfunction "FB_8") (pintype "passive"))
    )
    (net (code "58") (name "Net-(U68-FREQ)") (class "Default")
      (node (ref "R101") (pin "1") (pinfunction "1_1") (pintype "passive"))
      (node (ref "U68") (pin "9") (pinfunction "FREQ_9") (pintype "passive"))
    )
    (net (code "59") (name "Net-(U68-SS)") (class "Default")
      (node (ref "C100") (pin "2") (pinfunction "2_2") (pintype "passive"))
      (node (ref "U68") (pin "4") (pinfunction "SS_4") (pintype "passive"))
    )
    (net (code "60") (name "Net-(U71-2)") (class "Default")
      (node (ref "U68") (pin "1") (pinfunction "SW_1") (pintype "passive"))
      (node (ref "U68") (pin "15") (pinfunction "SW_15") (pintype "passive"))
      (node (ref "U68") (pin "16") (pinfunction "SW_16") (pintype "passive"))
      (node (ref "U71") (pin "1") (pinfunction "2_1") (pintype "passive"))
      (node (ref "U71") (pin "3") (pinfunction "4_3") (pintype "passive"))
    )
    (net (code "61") (name "unconnected-(LED2-DOUT-Pad2)") (class "Default")
      (node (ref "LED2") (pin "2") (pinfunction "DOUT_2") (pintype "passive"))
    )
    (net (code "62") (name "unconnected-(M1-Pad1)") (class "Default")
      (node (ref "M1") (pin "1") (pinfunction "1_1") (pintype "passive"))
    )
    (net (code "63") (name "unconnected-(M2-Pad1)") (class "Default")
      (node (ref "M2") (pin "1") (pinfunction "1_1") (pintype "passive"))
    )
    (net (code "64") (name "unconnected-(M3-Pad1)") (class "Default")
      (node (ref "M3") (pin "1") (pinfunction "1_1") (pintype "passive"))
    )
    (net (code "65") (name "unconnected-(M4-Pad1)") (class "Default")
      (node (ref "M4") (pin "1") (pinfunction "1_1") (pintype "passive"))
    )
    (net (code "66") (name "unconnected-(TP1-Pad1)") (class "Default")
      (node (ref "TP1") (pin "1") (pinfunction "1_1") (pintype "passive"))
    )
    (net (code "67") (name "unconnected-(U1-Pad1)") (class "Default")
      (node (ref "U1") (pin "1") (pinfunction "1_1") (pintype "passive+no_connect"))
    )
    (net (code "68") (name "unconnected-(U1-Pad6)") (class "Default")
      (node (ref "U1") (pin "6") (pinfunction "6_6") (pintype "passive"))
    )
    (net (code "69") (name "unconnected-(U1-Pad11)") (class "Default")
      (node (ref "U1") (pin "11") (pinfunction "11_11") (pintype "passive"))
    )
    (net (code "70") (name "unconnected-(U12-CTS#-Pad9)") (class "Default")
      (node (ref "U12") (pin "9") (pinfunction "CTS#_9") (pintype "passive"))
    )
    (net (code "71") (name "unconnected-(U12-DCD#-Pad12)") (class "Default")
      (node (ref "U12") (pin "12") (pinfunction "DCD#_12") (pintype "passive"))
    )
    (net (code "72") (name "unconnected-(U12-DSR#-Pad10)") (class "Default")
      (node (ref "U12") (pin "10") (pinfunction "DSR#_10") (pintype "passive"))
    )
    (net (code "73") (name "unconnected-(U12-NC.-Pad7)") (class "Default")
      (node (ref "U12") (pin "7") (pinfunction "NC._7") (pintype "passive"))
    )
    (net (code "74") (name "unconnected-(U12-NC.-Pad8)") (class "Default")
      (node (ref "U12") (pin "8") (pinfunction "NC._8") (pintype "passive"))
    )
    (net (code "75") (name "unconnected-(U12-R232-Pad15)") (class "Default")
      (node (ref "U12") (pin "15") (pinfunction "R232_15") (pintype "passive"))
    )
    (net (code "76") (name "unconnected-(U12-RI#-Pad11)") (class "Default")
      (node (ref "U12") (pin "11") (pinfunction "RI#_11") (pintype "passive"))
    )
    (net (code "77") (name "unconnected-(U18-FOE-Pad7)") (class "Default")
      (node (ref "U18") (pin "7") (pinfunction "FOE_7") (pintype "passive+no_connect"))
    )
    (net (code "78") (name "unconnected-(U18-FOUT-Pad3)") (class "Default")
      (node (ref "U18") (pin "3") (pinfunction "FOUT_3") (pintype "passive+no_connect"))
    )
    (net (code "79") (name "unconnected-(U18-INT#-Pad10)") (class "Default")
      (node (ref "U18") (pin "10") (pinfunction "INT#_10") (pintype "passive+no_connect"))
    )
    (net (code "80") (name "unconnected-(U18-NC-Pad4)") (class "Default")
      (node (ref "U18") (pin "4") (pinfunction "NC_4") (pintype "passive+no_connect"))
    )
    (net (code "81") (name "unconnected-(U18-NC-Pad8)") (class "Default")
      (node (ref "U18") (pin "8") (pinfunction "NC_8") (pintype "passive+no_connect"))
    )
    (net (code "82") (name "unconnected-(U18-NC-Pad9)") (class "Default")
      (node (ref "U18") (pin "9") (pinfunction "NC_9") (pintype "passive+no_connect"))
    )
    (net (code "83") (name "unconnected-(U18-NC-Pad14)") (class "Default")
      (node (ref "U18") (pin "14") (pinfunction "NC_14") (pintype "passive+no_connect"))
    )
    (net (code "84") (name "unconnected-(U18-T1-Pad1)") (class "Default")
      (node (ref "U18") (pin "1") (pinfunction "T1_1") (pintype "passive+no_connect"))
    )
    (net (code "85") (name "unconnected-(U18-T2-Pad12)") (class "Default")
      (node (ref "U18") (pin "12") (pinfunction "T2_12") (pintype "passive+no_connect"))
    )
    (net (code "86") (name "unconnected-(U18-TEST-Pad5)") (class "Default")
      (node (ref "U18") (pin "5") (pinfunction "TEST_5") (pintype "passive+no_connect"))
    )
    (net (code "87") (name "unconnected-(U68-EP-Pad17)") (class "Default")
      (node (ref "U68") (pin "17") (pinfunction "EP_17") (pintype "passive"))
    )
    (net (code "88") (name "unconnected-(U72-NC-Pad4)") (class "Default")
      (node (ref "U72") (pin "4") (pinfunction "NC_4") (pintype "passive+no_connect"))
    )
    (net (code "89") (name "unconnected-(U72-NC-Pad7)") (class "Default")
      (node (ref "U72") (pin "7") (pinfunction "NC_7") (pintype "passive+no_connect"))
    )
    (net (code "90") (name "unconnected-(U72-NC-Pad9)") (class "Default")
      (node (ref "U72") (pin "9") (pinfunction "NC_9") (pintype "passive+no_connect"))
    )
    (net (code "91") (name "unconnected-(U72-NC-Pad10)") (class "Default")
      (node (ref "U72") (pin "10") (pinfunction "NC_10") (pintype "passive+no_connect"))
    )
    (net (code "92") (name "unconnected-(U72-NC-Pad15)") (class "Default")
      (node (ref "U72") (pin "15") (pinfunction "NC_15") (pintype "passive+no_connect"))
    )
    (net (code "93") (name "unconnected-(U72-NC-Pad17)") (class "Default")
      (node (ref "U72") (pin "17") (pinfunction "NC_17") (pintype "passive+no_connect"))
    )
    (net (code "94") (name "unconnected-(U72-NC-Pad24)") (class "Default")
      (node (ref "U72") (pin "24") (pinfunction "NC_24") (pintype "passive+no_connect"))
    )
    (net (code "95") (name "unconnected-(U72-NC-Pad25)") (class "Default")
      (node (ref "U72") (pin "25") (pinfunction "NC_25") (pintype "passive+no_connect"))
    )
    (net (code "96") (name "unconnected-(U72-NC-Pad28)") (class "Default")
      (node (ref "U72") (pin "28") (pinfunction "NC_28") (pintype "passive+no_connect"))
    )
    (net (code "97") (name "unconnected-(U72-NC-Pad29)") (class "Default")
      (node (ref "U72") (pin "29") (pinfunction "NC_29") (pintype "passive+no_connect"))
    )
    (net (code "98") (name "unconnected-(U72-NC-Pad32)") (class "Default")
      (node (ref "U72") (pin "32") (pinfunction "NC_32") (pintype "passive+no_connect"))
    )
    (net (code "99") (name "unconnected-(U72-NC-Pad33)") (class "Default")
      (node (ref "U72") (pin "33") (pinfunction "NC_33") (pintype "passive+no_connect"))
    )
    (net (code "100") (name "unconnected-(U72-NC-Pad34)") (class "Default")
      (node (ref "U72") (pin "34") (pinfunction "NC_34") (pintype "passive+no_connect"))
    )
    (net (code "101") (name "unconnected-(U72-NC-Pad35)") (class "Default")
      (node (ref "U72") (pin "35") (pinfunction "NC_35") (pintype "passive+no_connect"))
    )
    (net (code "102") (name "unconnected-(USB2-GND-Pad13)") (class "Default")
      (node (ref "USB2") (pin "13") (pinfunction "GND_13") (pintype "passive"))
    )
    (net (code "103") (name "unconnected-(USB2-GND-Pad14)") (class "Default")
      (node (ref "USB2") (pin "14") (pinfunction "GND_14") (pintype "passive"))
    )
    (net (code "104") (name "unconnected-(USB2-GND-Pad15)") (class "Default")
      (node (ref "USB2") (pin "15") (pinfunction "GND_15") (pintype "passive"))
    )
    (net (code "105") (name "unconnected-(USB2-GND-Pad16)") (class "Default")
      (node (ref "USB2") (pin "16") (pinfunction "GND_16") (pintype "passive"))
    )
    (net (code "106") (name "unconnected-(USB2-SBU1-PadA8)") (class "Default")
      (node (ref "USB2") (pin "A8") (pinfunction "SBU1_A8") (pintype "passive+no_connect"))
    )
    (net (code "107") (name "unconnected-(USB2-SBU2-PadB8)") (class "Default")
      (node (ref "USB2") (pin "B8") (pinfunction "SBU2_B8") (pintype "passive+no_connect"))
    )
  )
)
